# ProDoc_Board1_2025-01-29.net
KiCad netlist of a schematic drawn in EasyEDA Pro
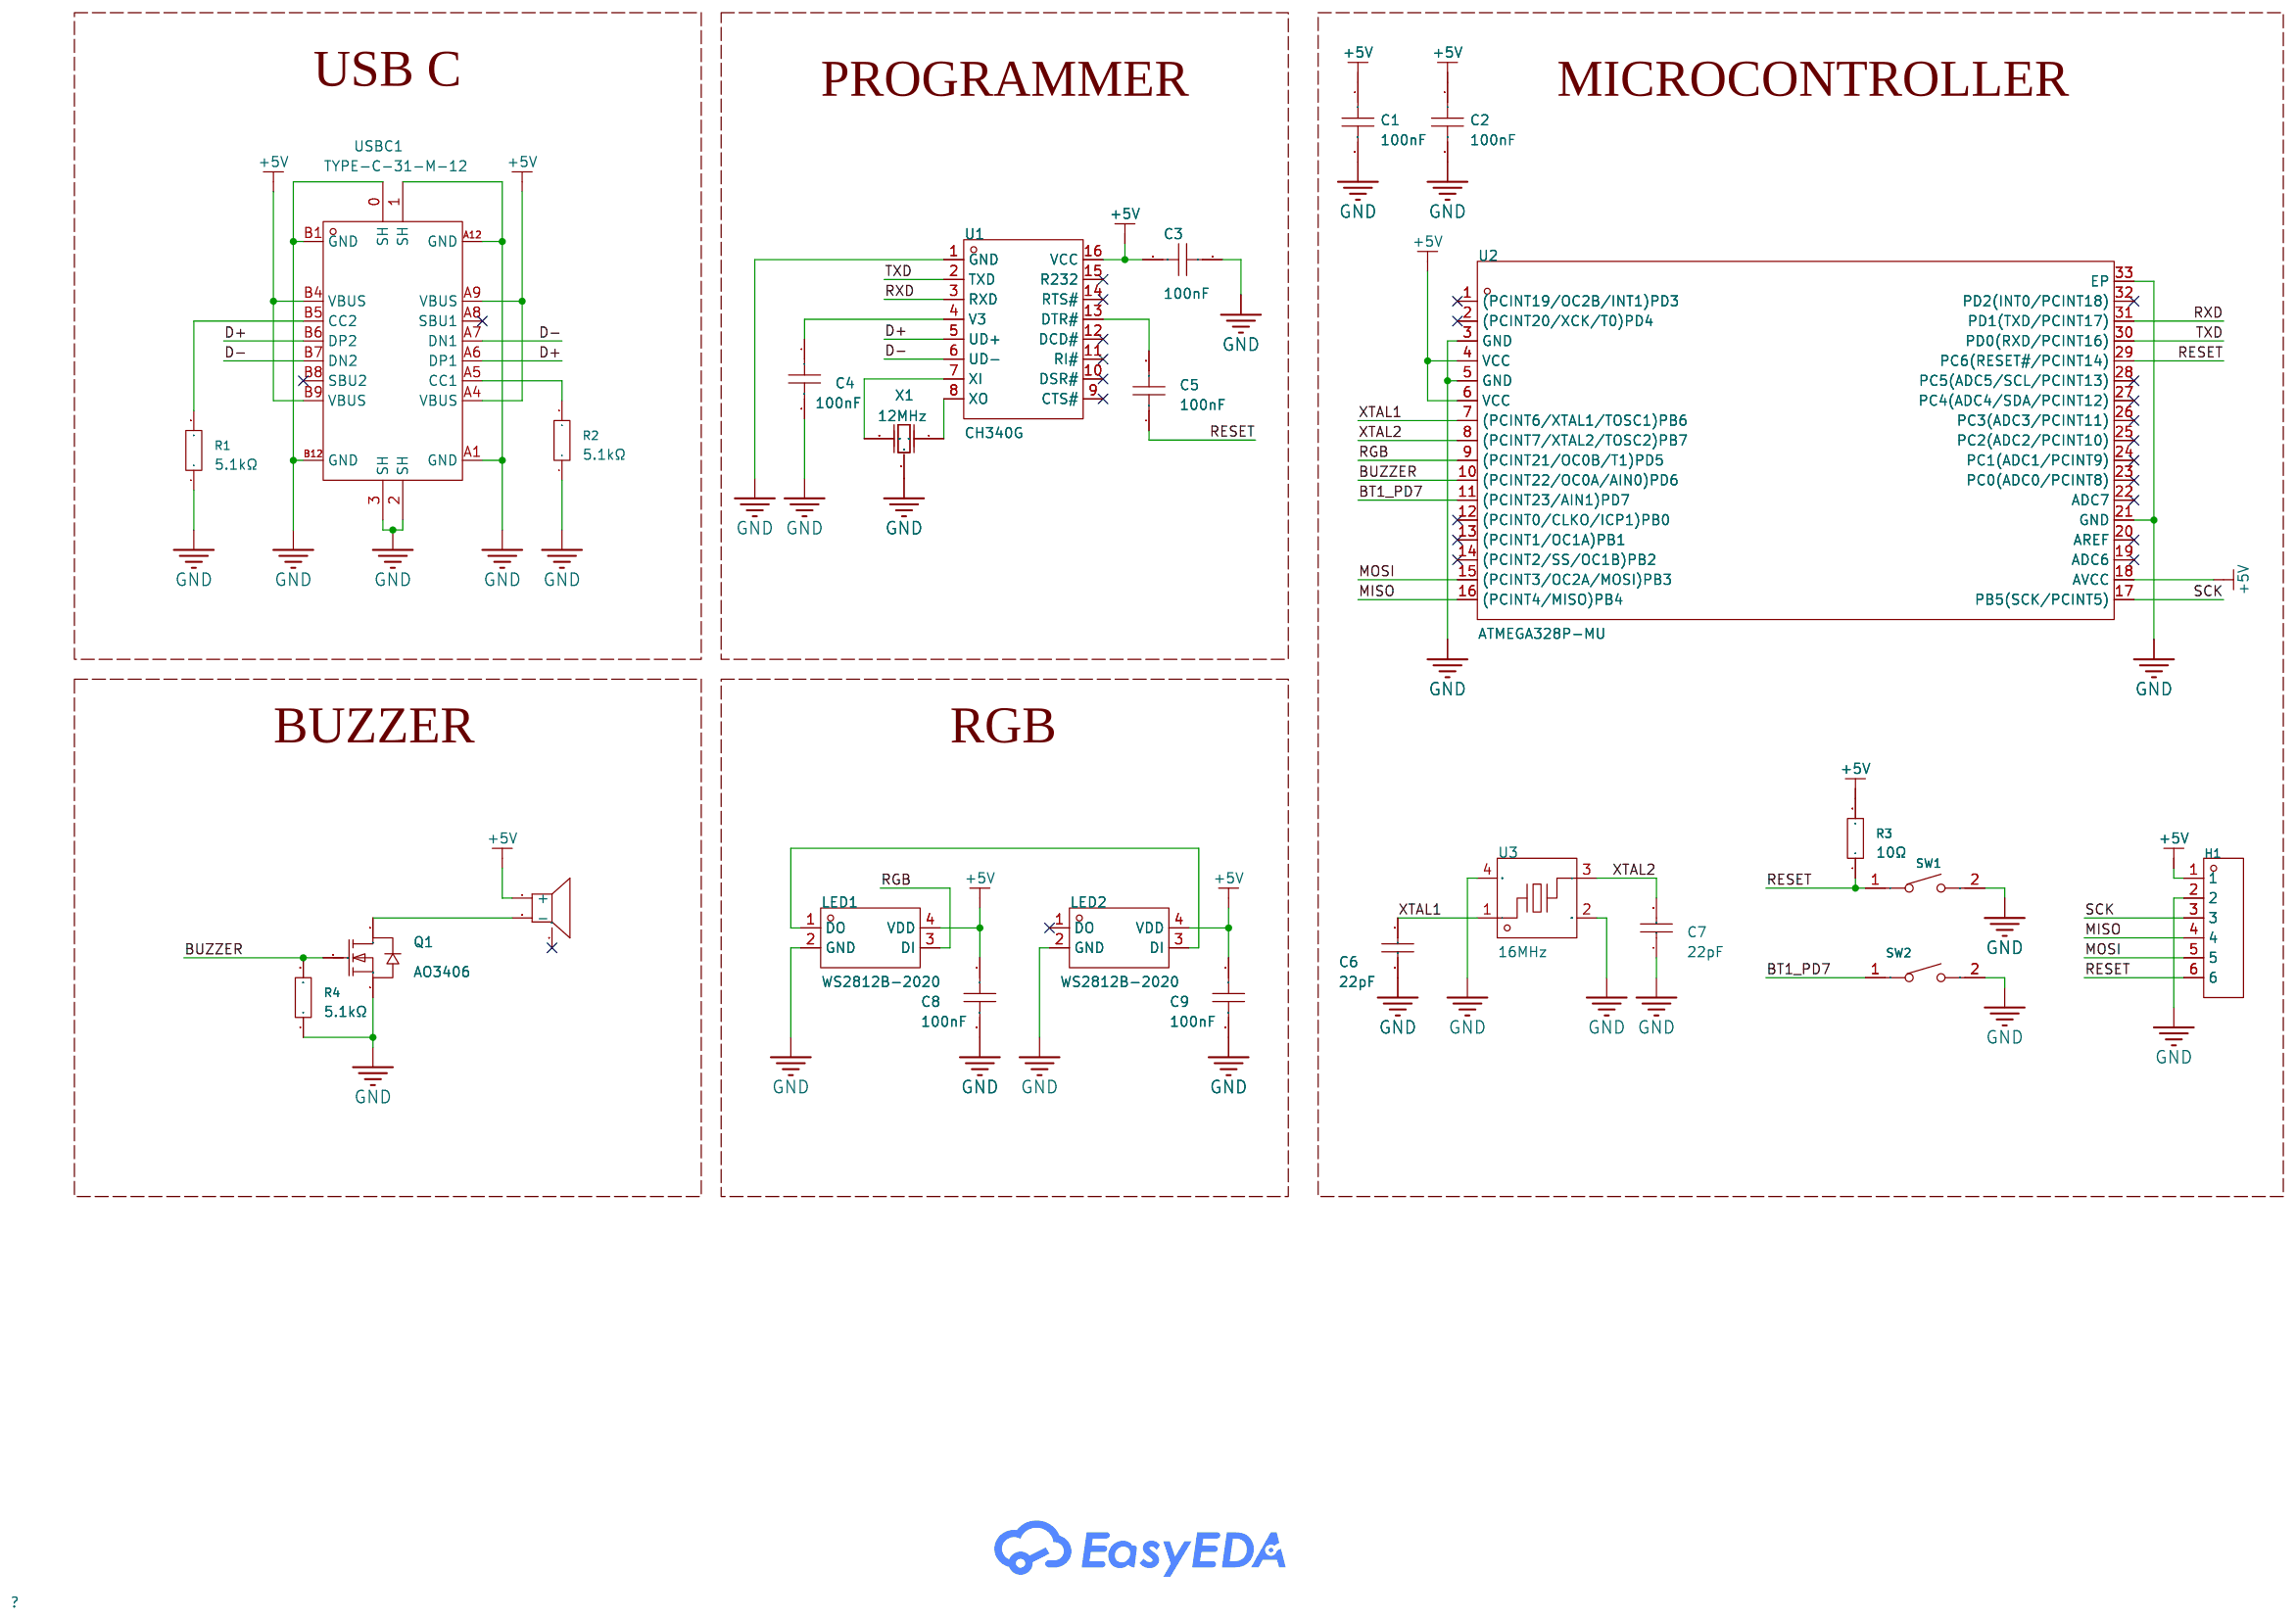
[diagram p0: schematic sheet]

(export (version "E")
  (design (tool "Eeschema 10.0.6"))
  (components
    (comp (ref "BUZZER1")
      (value "4kHz")
      (footprint "easyedapro:BUZ-SMD_L5.0-W5.5-P4.60")
      (fields (field (name "Manufacturer Part") "MLT-5020") (field (name "Manufacturer") "华能"))
      (libsource (lib "easyedapro") (part "MLT-5020"))
    )
    (comp (ref "C1")
      (value "100nF")
      (footprint "easyedapro:C0402")
      (fields
        (field (name "Manufacturer Part") "CL05B104KB54PNC")
        (field (name "Manufacturer") "SAMSUNG(三星)")
      )
      (libsource (lib "easyedapro") (part "CL05B104KB54PNC"))
    )
    (comp (ref "C2")
      (value "100nF")
      (footprint "easyedapro:C0402")
      (fields
        (field (name "Manufacturer Part") "CL05B104KB54PNC")
        (field (name "Manufacturer") "SAMSUNG(三星)")
      )
      (libsource (lib "easyedapro") (part "CL05B104KB54PNC"))
    )
    (comp (ref "C3")
      (value "100nF")
      (footprint "easyedapro:C0402")
      (fields
        (field (name "Manufacturer Part") "CL05B104KB54PNC")
        (field (name "Manufacturer") "SAMSUNG(三星)")
      )
      (libsource (lib "easyedapro") (part "CL05B104KB54PNC"))
    )
    (comp (ref "C4")
      (value "100nF")
      (footprint "easyedapro:C0402")
      (fields
        (field (name "Manufacturer Part") "CT41G-0402-2X1-16V-0.1μF-K(N)")
        (field (name "Manufacturer") "TORCH(火炬)")
      )
      (libsource (lib "easyedapro") (part "CT41G-0402-2X1-16V-0.1μF-K(N)"))
    )
    (comp (ref "C5")
      (value "100nF")
      (footprint "easyedapro:C0402")
      (fields
        (field (name "Manufacturer Part") "CL05B104KB54PNC")
        (field (name "Manufacturer") "SAMSUNG(三星)")
      )
      (libsource (lib "easyedapro") (part "CL05B104KB54PNC"))
    )
    (comp (ref "C6")
      (value "22pF")
      (footprint "easyedapro:C0402")
      (fields (field (name "Manufacturer Part") "0402CG220J500NT") (field (name "Manufacturer") "FH(风华)"))
      (libsource (lib "easyedapro") (part "0402CG220J500NT"))
    )
    (comp (ref "C7")
      (value "22pF")
      (footprint "easyedapro:C0402")
      (fields (field (name "Manufacturer Part") "0402CG220J500NT") (field (name "Manufacturer") "FH(风华)"))
      (libsource (lib "easyedapro") (part "0402CG220J500NT"))
    )
    (comp (ref "C8")
      (value "100nF")
      (footprint "easyedapro:C0402")
      (fields
        (field (name "Manufacturer Part") "CL05B104KB54PNC")
        (field (name "Manufacturer") "SAMSUNG(三星)")
      )
      (libsource (lib "easyedapro") (part "CL05B104KB54PNC"))
    )
    (comp (ref "C9")
      (value "100nF")
      (footprint "easyedapro:C0402")
      (fields
        (field (name "Manufacturer Part") "CL05B104KB54PNC")
        (field (name "Manufacturer") "SAMSUNG(三星)")
      )
      (libsource (lib "easyedapro") (part "CL05B104KB54PNC"))
    )
    (comp (ref "H1")
      (value "~")
      (footprint "easyedapro:HDR-TH_6P-P2.54-V-F")
      (libsource (lib "easyedapro") (part "Header-Female-2.54_1x6"))
    )
    (comp (ref "LED1")
      (value "WS2812B-2020")
      (footprint "easyedapro:LED-SMD_4P-L2.0-W2.0-TL_WS2812B-2020")
      (fields (field (name "Manufacturer") "worldsemi"))
      (libsource (lib "easyedapro") (part "WS2812B-2020"))
    )
    (comp (ref "LED2")
      (value "WS2812B-2020")
      (footprint "easyedapro:LED-SMD_4P-L2.0-W2.0-TL_WS2812B-2020")
      (fields (field (name "Manufacturer") "worldsemi"))
      (libsource (lib "easyedapro") (part "WS2812B-2020"))
    )
    (comp (ref "Q1")
      (value "AO3406")
      (footprint "easyedapro:SOT-23-3_L2.9-W1.6-P1.90-LS2.8-BR")
      (fields (field (name "Manufacturer") "MSKSEMI(美森科)"))
      (libsource (lib "easyedapro") (part "AO3406_C5379102"))
    )
    (comp (ref "R1")
      (value "5.1kΩ")
      (footprint "easyedapro:R0402")
      (fields
        (field (name "Manufacturer Part") "0402WGF5101TCE")
        (field (name "Manufacturer") "UNI-ROYAL(厚声)")
      )
      (libsource (lib "easyedapro") (part "0402WGF5101TCE"))
    )
    (comp (ref "R2")
      (value "5.1kΩ")
      (footprint "easyedapro:R0402")
      (fields
        (field (name "Manufacturer Part") "0402WGF5101TCE")
        (field (name "Manufacturer") "UNI-ROYAL(厚声)")
      )
      (libsource (lib "easyedapro") (part "0402WGF5101TCE"))
    )
    (comp (ref "R3")
      (value "10Ω")
      (footprint "easyedapro:R0402")
      (fields
        (field (name "Manufacturer Part") "0402WGF100JTCE")
        (field (name "Manufacturer") "UNI-ROYAL(厚声)")
      )
      (libsource (lib "easyedapro") (part "0402WGF100JTCE"))
    )
    (comp (ref "R4")
      (value "5.1kΩ")
      (footprint "easyedapro:R0402")
      (fields
        (field (name "Manufacturer Part") "0402WGF5101TCE")
        (field (name "Manufacturer") "UNI-ROYAL(厚声)")
      )
      (libsource (lib "easyedapro") (part "0402WGF5101TCE"))
    )
    (comp (ref "SW1")
      (value "TS-1088-AR02016")
      (footprint "easyedapro:SW-SMD_L3.9-W3.0-P4.45")
      (fields (field (name "Manufacturer") "XUNPU(讯普)"))
      (libsource (lib "easyedapro") (part "TS-1088-AR02016"))
    )
    (comp (ref "SW2")
      (value "TS-1088-AR02016")
      (footprint "easyedapro:SW-SMD_L3.9-W3.0-P4.45")
      (fields (field (name "Manufacturer") "XUNPU(讯普)"))
      (libsource (lib "easyedapro") (part "TS-1088-AR02016"))
    )
    (comp (ref "U1")
      (value "CH340G")
      (footprint "easyedapro:SOIC-16_L9.9-W3.9-P1.27-LS6.0-BL")
      (fields (field (name "Manufacturer") "WCH(南京沁恒)"))
      (libsource (lib "easyedapro") (part "CH340G"))
    )
    (comp (ref "U2")
      (value "ATMEGA328P-MU")
      (footprint "easyedapro:HVQFN-32_L5.0-W5.0-P0.50-TL-EP3.1")
      (fields (field (name "Manufacturer") "MICROCHIP(美国微芯)"))
      (libsource (lib "easyedapro") (part "ATMEGA328P-MU_C7499261"))
    )
    (comp (ref "U3")
      (value "16MHz")
      (footprint "easyedapro:CRYSTAL-SMD_4P-L3.2-W2.5-BL_SIT8008BI")
      (fields (field (name "Manufacturer Part") "S3216000222080C3") (field (name "Manufacturer") "JGHC(晶光华)"))
      (libsource (lib "easyedapro") (part "S3216000222080C3"))
    )
    (comp (ref "USBC1")
      (value "TYPE-C-31-M-12")
      (footprint "easyedapro:USB-C_SMD-TYPE-C-31-M-12")
      (fields (field (name "Manufacturer") "韩国韩荣"))
      (libsource (lib "easyedapro") (part "TYPE-C-31-M-12"))
    )
    (comp (ref "X1")
      (value "12MHz")
      (footprint "easyedapro:CRYSTAL-SMD_3P-L3.2-W1.3-P1.20-L-1")
      (fields
        (field (name "Manufacturer Part") "CSTNE12M0G550000R0")
        (field (name "Manufacturer") "muRata(村田)")
      )
      (libsource (lib "easyedapro") (part "CSTNE12M0G550000R0"))
    )
  )
  (nets
    (net (code "1") (name "+5V") (class "Default")
      (node (ref "BUZZER1") (pin "1") (pinfunction "+_1") (pintype "unspecified"))
      (node (ref "C1") (pin "1") (pinfunction "1_1") (pintype "input"))
      (node (ref "C2") (pin "1") (pinfunction "1_1") (pintype "input"))
      (node (ref "C3") (pin "2") (pinfunction "2_2") (pintype "input"))
      (node (ref "C8") (pin "1") (pinfunction "1_1") (pintype "input"))
      (node (ref "C9") (pin "1") (pinfunction "1_1") (pintype "input"))
      (node (ref "H1") (pin "1") (pinfunction "1_1") (pintype "input"))
      (node (ref "LED1") (pin "4") (pinfunction "VDD_4") (pintype "unspecified"))
      (node (ref "LED2") (pin "4") (pinfunction "VDD_4") (pintype "unspecified"))
      (node (ref "R3") (pin "2") (pinfunction "2_2") (pintype "input"))
      (node (ref "U1") (pin "16") (pinfunction "VCC_16") (pintype "unspecified"))
      (node (ref "U2") (pin "18") (pinfunction "AVCC_18") (pintype "unspecified"))
      (node (ref "U2") (pin "4") (pinfunction "VCC_4") (pintype "unspecified"))
      (node (ref "U2") (pin "6") (pinfunction "VCC_6") (pintype "unspecified"))
      (node (ref "USBC1") (pin "A4") (pinfunction "VBUS_A4") (pintype "unspecified"))
      (node (ref "USBC1") (pin "A9") (pinfunction "VBUS_A9") (pintype "unspecified"))
      (node (ref "USBC1") (pin "B4") (pinfunction "VBUS_B4") (pintype "unspecified"))
      (node (ref "USBC1") (pin "B9") (pinfunction "VBUS_B9") (pintype "unspecified"))
    )
    (net (code "2") (name "/BT1_PD7") (class "Default")
      (node (ref "SW2") (pin "1") (pinfunction "1_1") (pintype "input"))
      (node (ref "U2") (pin "11") (pinfunction "(PCINT23/AIN1)PD7_11") (pintype "unspecified"))
    )
    (net (code "3") (name "/BUZZER") (class "Default")
      (node (ref "Q1") (pin "1") (pinfunction "G_1") (pintype "unspecified"))
      (node (ref "R4") (pin "2") (pinfunction "2_2") (pintype "input"))
      (node (ref "U2") (pin "10") (pinfunction "(PCINT22/OC0A/AIN0)PD6_10") (pintype "unspecified"))
    )
    (net (code "4") (name "/D+") (class "Default")
      (node (ref "U1") (pin "5") (pinfunction "UD+_5") (pintype "unspecified"))
      (node (ref "USBC1") (pin "A6") (pinfunction "DP1_A6") (pintype "unspecified"))
      (node (ref "USBC1") (pin "B6") (pinfunction "DP2_B6") (pintype "unspecified"))
    )
    (net (code "5") (name "/D-") (class "Default")
      (node (ref "U1") (pin "6") (pinfunction "UD-_6") (pintype "unspecified"))
      (node (ref "USBC1") (pin "A7") (pinfunction "DN1_A7") (pintype "unspecified"))
      (node (ref "USBC1") (pin "B7") (pinfunction "DN2_B7") (pintype "unspecified"))
    )
    (net (code "6") (name "/MISO") (class "Default")
      (node (ref "H1") (pin "4") (pinfunction "4_4") (pintype "input"))
      (node (ref "U2") (pin "16") (pinfunction "(PCINT4/MISO)PB4_16") (pintype "unspecified"))
    )
    (net (code "7") (name "/MOSI") (class "Default")
      (node (ref "H1") (pin "5") (pinfunction "5_5") (pintype "input"))
      (node (ref "U2") (pin "15") (pinfunction "(PCINT3/OC2A/MOSI)PB3_15") (pintype "unspecified"))
    )
    (net (code "8") (name "/RESET") (class "Default")
      (node (ref "C5") (pin "1") (pinfunction "1_1") (pintype "input"))
      (node (ref "H1") (pin "6") (pinfunction "6_6") (pintype "input"))
      (node (ref "R3") (pin "1") (pinfunction "1_1") (pintype "input"))
      (node (ref "SW1") (pin "1") (pinfunction "1_1") (pintype "input"))
      (node (ref "U2") (pin "29") (pinfunction "PC6(RESET#/PCINT14)_29") (pintype "unspecified"))
    )
    (net (code "9") (name "/RGB") (class "Default")
      (node (ref "LED1") (pin "3") (pinfunction "DI_3") (pintype "unspecified"))
      (node (ref "U2") (pin "9") (pinfunction "(PCINT21/OC0B/T1)PD5_9") (pintype "unspecified"))
    )
    (net (code "10") (name "/RXD") (class "Default")
      (node (ref "U1") (pin "3") (pinfunction "RXD_3") (pintype "unspecified"))
      (node (ref "U2") (pin "31") (pinfunction "PD1(TXD/PCINT17)_31") (pintype "unspecified"))
    )
    (net (code "11") (name "/SCK") (class "Default")
      (node (ref "H1") (pin "3") (pinfunction "3_3") (pintype "input"))
      (node (ref "U2") (pin "17") (pinfunction "PB5(SCK/PCINT5)_17") (pintype "unspecified"))
    )
    (net (code "12") (name "/TXD") (class "Default")
      (node (ref "U1") (pin "2") (pinfunction "TXD_2") (pintype "unspecified"))
      (node (ref "U2") (pin "30") (pinfunction "PD0(RXD/PCINT16)_30") (pintype "unspecified"))
    )
    (net (code "13") (name "/XTAL1") (class "Default")
      (node (ref "C6") (pin "2") (pinfunction "2_2") (pintype "input"))
      (node (ref "U2") (pin "7") (pinfunction "(PCINT6/XTAL1/TOSC1)PB6_7") (pintype "unspecified"))
      (node (ref "U3") (pin "1") (pinfunction "1_1") (pintype "input"))
    )
    (net (code "14") (name "/XTAL2") (class "Default")
      (node (ref "C7") (pin "2") (pinfunction "2_2") (pintype "input"))
      (node (ref "U2") (pin "8") (pinfunction "(PCINT7/XTAL2/TOSC2)PB7_8") (pintype "unspecified"))
      (node (ref "U3") (pin "3") (pinfunction "3_3") (pintype "input"))
    )
    (net (code "15") (name "GND") (class "Default")
      (node (ref "C1") (pin "2") (pinfunction "2_2") (pintype "input"))
      (node (ref "C2") (pin "2") (pinfunction "2_2") (pintype "input"))
      (node (ref "C3") (pin "1") (pinfunction "1_1") (pintype "input"))
      (node (ref "C4") (pin "2") (pinfunction "2_2") (pintype "unspecified"))
      (node (ref "C6") (pin "1") (pinfunction "1_1") (pintype "input"))
      (node (ref "C7") (pin "1") (pinfunction "1_1") (pintype "input"))
      (node (ref "C8") (pin "2") (pinfunction "2_2") (pintype "input"))
      (node (ref "C9") (pin "2") (pinfunction "2_2") (pintype "input"))
      (node (ref "H1") (pin "2") (pinfunction "2_2") (pintype "input"))
      (node (ref "LED1") (pin "2") (pinfunction "GND_2") (pintype "unspecified"))
      (node (ref "LED2") (pin "2") (pinfunction "GND_2") (pintype "unspecified"))
      (node (ref "Q1") (pin "2") (pinfunction "S_2") (pintype "unspecified"))
      (node (ref "R1") (pin "1") (pinfunction "1_1") (pintype "input"))
      (node (ref "R2") (pin "1") (pinfunction "1_1") (pintype "input"))
      (node (ref "R4") (pin "1") (pinfunction "1_1") (pintype "input"))
      (node (ref "SW1") (pin "2") (pinfunction "2_2") (pintype "input"))
      (node (ref "SW2") (pin "2") (pinfunction "2_2") (pintype "input"))
      (node (ref "U1") (pin "1") (pinfunction "GND_1") (pintype "unspecified"))
      (node (ref "U2") (pin "21") (pinfunction "GND_21") (pintype "unspecified"))
      (node (ref "U2") (pin "3") (pinfunction "GND_3") (pintype "unspecified"))
      (node (ref "U2") (pin "33") (pinfunction "EP_33") (pintype "unspecified"))
      (node (ref "U2") (pin "5") (pinfunction "GND_5") (pintype "unspecified"))
      (node (ref "U3") (pin "2") (pinfunction "GND_2") (pintype "input"))
      (node (ref "U3") (pin "4") (pinfunction "GND_4") (pintype "input"))
      (node (ref "USBC1") (pin "0") (pinfunction "SH_0") (pintype "unspecified"))
      (node (ref "USBC1") (pin "1") (pinfunction "SH_1") (pintype "unspecified"))
      (node (ref "USBC1") (pin "2") (pinfunction "SH_2") (pintype "unspecified"))
      (node (ref "USBC1") (pin "3") (pinfunction "SH_3") (pintype "unspecified"))
      (node (ref "USBC1") (pin "A1") (pinfunction "GND_A1") (pintype "unspecified"))
      (node (ref "USBC1") (pin "A12") (pinfunction "GND_A12") (pintype "unspecified"))
      (node (ref "USBC1") (pin "B1") (pinfunction "GND_B1") (pintype "unspecified"))
      (node (ref "USBC1") (pin "B12") (pinfunction "GND_B12") (pintype "unspecified"))
      (node (ref "X1") (pin "2") (pinfunction "GND_2") (pintype "input"))
    )
    (net (code "16") (name "Net-(BUZZER1--)") (class "Default")
      (node (ref "BUZZER1") (pin "2") (pinfunction "-_2") (pintype "unspecified"))
      (node (ref "Q1") (pin "3") (pinfunction "D_3") (pintype "unspecified"))
    )
    (net (code "17") (name "Net-(LED1-DO)") (class "Default")
      (node (ref "LED1") (pin "1") (pinfunction "DO_1") (pintype "unspecified"))
      (node (ref "LED2") (pin "3") (pinfunction "DI_3") (pintype "unspecified"))
    )
    (net (code "18") (name "Net-(U1-DTR#)") (class "Default")
      (node (ref "C5") (pin "2") (pinfunction "2_2") (pintype "input"))
      (node (ref "U1") (pin "13") (pinfunction "DTR#_13") (pintype "unspecified"))
    )
    (net (code "19") (name "Net-(U1-V3)") (class "Default")
      (node (ref "C4") (pin "1") (pinfunction "1_1") (pintype "unspecified"))
      (node (ref "U1") (pin "4") (pinfunction "V3_4") (pintype "unspecified"))
    )
    (net (code "20") (name "Net-(U1-XI)") (class "Default")
      (node (ref "U1") (pin "7") (pinfunction "XI_7") (pintype "unspecified"))
      (node (ref "X1") (pin "3") (pinfunction "OUTPUT_3") (pintype "input"))
    )
    (net (code "21") (name "Net-(U1-XO)") (class "Default")
      (node (ref "U1") (pin "8") (pinfunction "XO_8") (pintype "unspecified"))
      (node (ref "X1") (pin "1") (pinfunction "INPUT_1") (pintype "input"))
    )
    (net (code "22") (name "Net-(USBC1-CC1)") (class "Default")
      (node (ref "R2") (pin "2") (pinfunction "2_2") (pintype "input"))
      (node (ref "USBC1") (pin "A5") (pinfunction "CC1_A5") (pintype "unspecified"))
    )
    (net (code "23") (name "Net-(USBC1-CC2)") (class "Default")
      (node (ref "R1") (pin "2") (pinfunction "2_2") (pintype "input"))
      (node (ref "USBC1") (pin "B5") (pinfunction "CC2_B5") (pintype "unspecified"))
    )
    (net (code "24") (name "unconnected-(BUZZER1-NC-Pad3)") (class "Default")
      (node (ref "BUZZER1") (pin "3") (pinfunction "NC_3") (pintype "unspecified+no_connect"))
    )
    (net (code "25") (name "unconnected-(LED2-DO-Pad1)") (class "Default")
      (node (ref "LED2") (pin "1") (pinfunction "DO_1") (pintype "unspecified+no_connect"))
    )
    (net (code "26") (name "unconnected-(U1-CTS#-Pad9)") (class "Default")
      (node (ref "U1") (pin "9") (pinfunction "CTS#_9") (pintype "unspecified+no_connect"))
    )
    (net (code "27") (name "unconnected-(U1-DCD#-Pad12)") (class "Default")
      (node (ref "U1") (pin "12") (pinfunction "DCD#_12") (pintype "unspecified+no_connect"))
    )
    (net (code "28") (name "unconnected-(U1-DSR#-Pad10)") (class "Default")
      (node (ref "U1") (pin "10") (pinfunction "DSR#_10") (pintype "unspecified+no_connect"))
    )
    (net (code "29") (name "unconnected-(U1-R232-Pad15)") (class "Default")
      (node (ref "U1") (pin "15") (pinfunction "R232_15") (pintype "unspecified+no_connect"))
    )
    (net (code "30") (name "unconnected-(U1-RI#-Pad11)") (class "Default")
      (node (ref "U1") (pin "11") (pinfunction "RI#_11") (pintype "unspecified+no_connect"))
    )
    (net (code "31") (name "unconnected-(U1-RTS#-Pad14)") (class "Default")
      (node (ref "U1") (pin "14") (pinfunction "RTS#_14") (pintype "unspecified+no_connect"))
    )
    (net (code "32") (name "unconnected-(U2-(PCINT0{slash}CLKO{slash}ICP1)PB0-Pad12)") (class "Default")
      (node (ref "U2") (pin "12") (pinfunction "(PCINT0/CLKO/ICP1)PB0_12") (pintype "unspecified+no_connect"))
    )
    (net (code "33") (name "unconnected-(U2-(PCINT1{slash}OC1A)PB1-Pad13)") (class "Default")
      (node (ref "U2") (pin "13") (pinfunction "(PCINT1/OC1A)PB1_13") (pintype "unspecified+no_connect"))
    )
    (net (code "34") (name "unconnected-(U2-(PCINT2{slash}SS{slash}OC1B)PB2-Pad14)") (class "Default")
      (node (ref "U2") (pin "14") (pinfunction "(PCINT2/SS/OC1B)PB2_14") (pintype "unspecified+no_connect"))
    )
    (net (code "35") (name "unconnected-(U2-(PCINT19{slash}OC2B{slash}INT1)PD3-Pad1)") (class "Default")
      (node (ref "U2") (pin "1") (pinfunction "(PCINT19/OC2B/INT1)PD3_1") (pintype "unspecified+no_connect"))
    )
    (net (code "36") (name "unconnected-(U2-(PCINT20{slash}XCK{slash}T0)PD4-Pad2)") (class "Default")
      (node (ref "U2") (pin "2") (pinfunction "(PCINT20/XCK/T0)PD4_2") (pintype "unspecified+no_connect"))
    )
    (net (code "37") (name "unconnected-(U2-ADC6-Pad19)") (class "Default")
      (node (ref "U2") (pin "19") (pinfunction "ADC6_19") (pintype "unspecified+no_connect"))
    )
    (net (code "38") (name "unconnected-(U2-ADC7-Pad22)") (class "Default")
      (node (ref "U2") (pin "22") (pinfunction "ADC7_22") (pintype "unspecified+no_connect"))
    )
    (net (code "39") (name "unconnected-(U2-AREF-Pad20)") (class "Default")
      (node (ref "U2") (pin "20") (pinfunction "AREF_20") (pintype "unspecified+no_connect"))
    )
    (net (code "40") (name "unconnected-(U2-PC0(ADC0{slash}PCINT8)-Pad23)") (class "Default")
      (node (ref "U2") (pin "23") (pinfunction "PC0(ADC0/PCINT8)_23") (pintype "unspecified+no_connect"))
    )
    (net (code "41") (name "unconnected-(U2-PC1(ADC1{slash}PCINT9)-Pad24)") (class "Default")
      (node (ref "U2") (pin "24") (pinfunction "PC1(ADC1/PCINT9)_24") (pintype "unspecified+no_connect"))
    )
    (net (code "42") (name "unconnected-(U2-PC2(ADC2{slash}PCINT10)-Pad25)") (class "Default")
      (node (ref "U2") (pin "25") (pinfunction "PC2(ADC2/PCINT10)_25") (pintype "unspecified+no_connect"))
    )
    (net (code "43") (name "unconnected-(U2-PC3(ADC3{slash}PCINT11)-Pad26)") (class "Default")
      (node (ref "U2") (pin "26") (pinfunction "PC3(ADC3/PCINT11)_26") (pintype "unspecified+no_connect"))
    )
    (net (code "44") (name "unconnected-(U2-PC4(ADC4{slash}SDA{slash}PCINT12)-Pad27)") (class "Default")
      (node (ref "U2") (pin "27") (pinfunction "PC4(ADC4/SDA/PCINT12)_27") (pintype "unspecified+no_connect"))
    )
    (net (code "45") (name "unconnected-(U2-PC5(ADC5{slash}SCL{slash}PCINT13)-Pad28)") (class "Default")
      (node (ref "U2") (pin "28") (pinfunction "PC5(ADC5/SCL/PCINT13)_28") (pintype "unspecified+no_connect"))
    )
    (net (code "46") (name "unconnected-(U2-PD2(INT0{slash}PCINT18)-Pad32)") (class "Default")
      (node (ref "U2") (pin "32") (pinfunction "PD2(INT0/PCINT18)_32") (pintype "unspecified+no_connect"))
    )
    (net (code "47") (name "unconnected-(USBC1-SBU1-PadA8)") (class "Default")
      (node (ref "USBC1") (pin "A8") (pinfunction "SBU1_A8") (pintype "unspecified+no_connect"))
    )
    (net (code "48") (name "unconnected-(USBC1-SBU2-PadB8)") (class "Default")
      (node (ref "USBC1") (pin "B8") (pinfunction "SBU2_B8") (pintype "unspecified+no_connect"))
    )
  )
)
